# SSB_Transceiver_Speaker_Amplifier.net
KiCad netlist of a schematic drawn in EAGLE
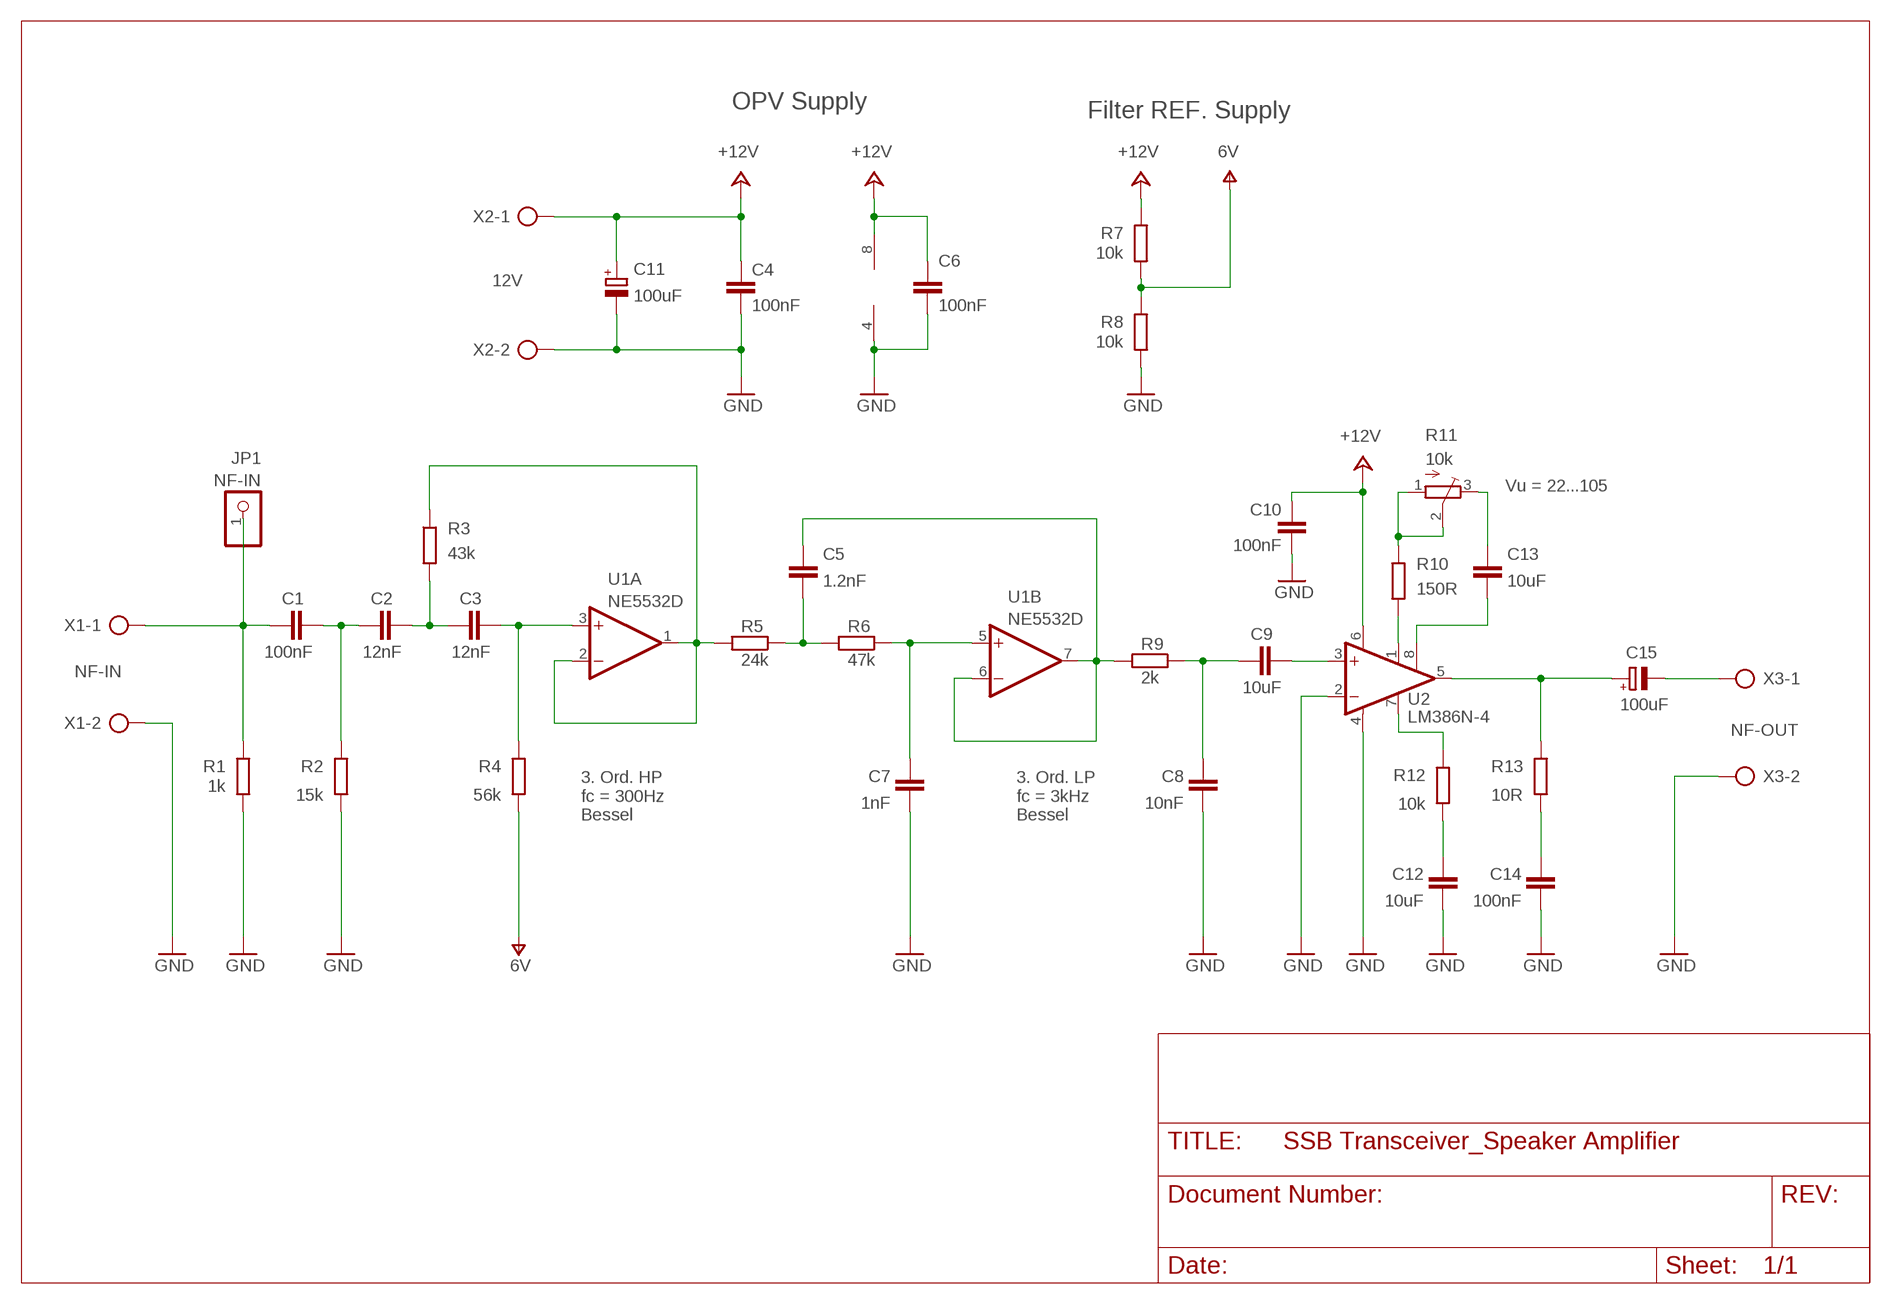
[diagram p0: schematic, sheet 1]

(export (version "E")
  (design (tool "Eeschema 10.0.6"))
  (components
    (comp (ref "C1")
      (value "100nF")
      (footprint "eagle-import:C0805")
      (libsource (lib "eagle-import") (part "C-EUC0805"))
    )
    (comp (ref "C2")
      (value "12nF")
      (footprint "eagle-import:C0805")
      (libsource (lib "eagle-import") (part "C-EUC0805"))
    )
    (comp (ref "C3")
      (value "12nF")
      (footprint "eagle-import:C0805")
      (libsource (lib "eagle-import") (part "C-EUC0805"))
    )
    (comp (ref "C4")
      (value "100nF")
      (footprint "eagle-import:C0805")
      (libsource (lib "eagle-import") (part "C-EUC0805"))
    )
    (comp (ref "C5")
      (value "1.2nF")
      (footprint "eagle-import:C0805")
      (libsource (lib "eagle-import") (part "C-EUC0805"))
    )
    (comp (ref "C6")
      (value "100nF")
      (footprint "eagle-import:C0805")
      (libsource (lib "eagle-import") (part "C-EUC0805"))
    )
    (comp (ref "C7")
      (value "1nF")
      (footprint "eagle-import:C0805")
      (libsource (lib "eagle-import") (part "C-EUC0805"))
    )
    (comp (ref "C8")
      (value "10nF")
      (footprint "eagle-import:C0805")
      (libsource (lib "eagle-import") (part "C-EUC0805"))
    )
    (comp (ref "C9")
      (value "10uF")
      (footprint "eagle-import:C0805")
      (libsource (lib "eagle-import") (part "C-EUC0805"))
    )
    (comp (ref "C10")
      (value "100nF")
      (footprint "eagle-import:C0805")
      (libsource (lib "eagle-import") (part "C-EUC0805"))
    )
    (comp (ref "C11")
      (value "100uF")
      (footprint "eagle-import:E2,5-6")
      (libsource (lib "eagle-import") (part "CPOL-EUE2.5-6"))
    )
    (comp (ref "C12")
      (value "10uF")
      (footprint "eagle-import:C0805")
      (libsource (lib "eagle-import") (part "C-EUC0805"))
    )
    (comp (ref "C13")
      (value "10uF")
      (footprint "eagle-import:C0805")
      (libsource (lib "eagle-import") (part "C-EUC0805"))
    )
    (comp (ref "C14")
      (value "100nF")
      (footprint "eagle-import:C0805")
      (libsource (lib "eagle-import") (part "C-EUC0805"))
    )
    (comp (ref "C15")
      (value "100uF")
      (footprint "eagle-import:E2,5-6")
      (libsource (lib "eagle-import") (part "CPOL-EUE2.5-6"))
    )
    (comp (ref "JP1")
      (value "NF-IN")
      (footprint "eagle-import:1X01")
      (libsource (lib "eagle-import") (part "PINHD-1X1"))
    )
    (comp (ref "R1")
      (value "1k")
      (footprint "eagle-import:R0805")
      (libsource (lib "eagle-import") (part "R-EU_R0805"))
    )
    (comp (ref "R2")
      (value "15k")
      (footprint "eagle-import:R0805")
      (libsource (lib "eagle-import") (part "R-EU_R0805"))
    )
    (comp (ref "R3")
      (value "43k")
      (footprint "eagle-import:R0805")
      (libsource (lib "eagle-import") (part "R-EU_R0805"))
    )
    (comp (ref "R4")
      (value "56k")
      (footprint "eagle-import:R0805")
      (libsource (lib "eagle-import") (part "R-EU_R0805"))
    )
    (comp (ref "R5")
      (value "24k")
      (footprint "eagle-import:R0805")
      (libsource (lib "eagle-import") (part "R-EU_R0805"))
    )
    (comp (ref "R6")
      (value "47k")
      (footprint "eagle-import:R0805")
      (libsource (lib "eagle-import") (part "R-EU_R0805"))
    )
    (comp (ref "R7")
      (value "10k")
      (footprint "eagle-import:R0805")
      (libsource (lib "eagle-import") (part "R-EU_R0805"))
    )
    (comp (ref "R8")
      (value "10k")
      (footprint "eagle-import:R0805")
      (libsource (lib "eagle-import") (part "R-EU_R0805"))
    )
    (comp (ref "R9")
      (value "2k")
      (footprint "eagle-import:R0805")
      (libsource (lib "eagle-import") (part "R-EU_R0805"))
    )
    (comp (ref "R10")
      (value "150R")
      (footprint "eagle-import:R0805")
      (libsource (lib "eagle-import") (part "R-EU_R0805"))
    )
    (comp (ref "R11")
      (value "10k")
      (footprint "eagle-import:3223G")
      (libsource (lib "eagle-import") (part "TRIM_EU-3223G"))
    )
    (comp (ref "R12")
      (value "10k")
      (footprint "eagle-import:R0805")
      (libsource (lib "eagle-import") (part "R-EU_R0805"))
    )
    (comp (ref "R13")
      (value "10R")
      (footprint "eagle-import:R0805")
      (libsource (lib "eagle-import") (part "R-EU_R0805"))
    )
    (comp (ref "U1")
      (value "NE5532D")
      (footprint "eagle-import:SO08")
      (libsource (lib "eagle-import") (part "NE5532D"))
    )
    (comp (ref "U2")
      (value "LM386N-4")
      (footprint "eagle-import:DIL08")
      (libsource (lib "eagle-import") (part "LM386?-N4"))
    )
    (comp (ref "X1")
      (value "NF-IN")
      (footprint "eagle-import:AK300_2")
      (libsource (lib "eagle-import") (part "AK300/2"))
    )
    (comp (ref "X2")
      (value "12V")
      (footprint "eagle-import:AK300_2")
      (libsource (lib "eagle-import") (part "AK300/2"))
    )
    (comp (ref "X3")
      (value "NF-OUT")
      (footprint "eagle-import:AK300_2")
      (libsource (lib "eagle-import") (part "AK300/2"))
    )
  )
  (nets
    (net (code "1") (name "+12V") (class "Default")
      (node (ref "C10") (pin "2") (pinfunction "2_2") (pintype "passive"))
      (node (ref "C11") (pin "+") (pinfunction "+_+") (pintype "passive"))
      (node (ref "C4") (pin "2") (pinfunction "2_2") (pintype "passive"))
      (node (ref "C6") (pin "2") (pinfunction "2_2") (pintype "passive"))
      (node (ref "R7") (pin "1") (pinfunction "1_1") (pintype "passive"))
      (node (ref "U1") (pin "8") (pinfunction "V+_8") (pintype "power_in"))
      (node (ref "U2") (pin "6") (pinfunction "VS_6") (pintype "power_in"))
      (node (ref "X2") (pin "1") (pinfunction "KL_1") (pintype "passive"))
    )
    (net (code "2") (name "6V") (class "Default")
      (node (ref "R4") (pin "2") (pinfunction "2_2") (pintype "passive"))
      (node (ref "R7") (pin "2") (pinfunction "2_2") (pintype "passive"))
      (node (ref "R8") (pin "1") (pinfunction "1_1") (pintype "passive"))
    )
    (net (code "3") (name "GND") (class "Default")
      (node (ref "C10") (pin "1") (pinfunction "1_1") (pintype "passive"))
      (node (ref "C11") (pin "-") (pinfunction "-_-") (pintype "passive"))
      (node (ref "C12") (pin "1") (pinfunction "1_1") (pintype "passive"))
      (node (ref "C14") (pin "1") (pinfunction "1_1") (pintype "passive"))
      (node (ref "C4") (pin "1") (pinfunction "1_1") (pintype "passive"))
      (node (ref "C6") (pin "1") (pinfunction "1_1") (pintype "passive"))
      (node (ref "C7") (pin "1") (pinfunction "1_1") (pintype "passive"))
      (node (ref "C8") (pin "1") (pinfunction "1_1") (pintype "passive"))
      (node (ref "R1") (pin "2") (pinfunction "2_2") (pintype "passive"))
      (node (ref "R2") (pin "2") (pinfunction "2_2") (pintype "passive"))
      (node (ref "R8") (pin "2") (pinfunction "2_2") (pintype "passive"))
      (node (ref "U1") (pin "4") (pinfunction "V-_4") (pintype "power_in"))
      (node (ref "U2") (pin "2") (pinfunction "-IN_2") (pintype "input"))
      (node (ref "U2") (pin "4") (pinfunction "GND_4") (pintype "power_in"))
      (node (ref "X1") (pin "2") (pinfunction "KL_2") (pintype "passive"))
      (node (ref "X2") (pin "2") (pinfunction "KL_2") (pintype "passive"))
      (node (ref "X3") (pin "2") (pinfunction "KL_2") (pintype "passive"))
    )
    (net (code "4") (name "Net-(C1-Pad2)") (class "Default")
      (node (ref "C1") (pin "2") (pinfunction "2_2") (pintype "passive"))
      (node (ref "C2") (pin "1") (pinfunction "1_1") (pintype "passive"))
      (node (ref "R2") (pin "1") (pinfunction "1_1") (pintype "passive"))
    )
    (net (code "5") (name "Net-(C2-Pad2)") (class "Default")
      (node (ref "C2") (pin "2") (pinfunction "2_2") (pintype "passive"))
      (node (ref "C3") (pin "1") (pinfunction "1_1") (pintype "passive"))
      (node (ref "R3") (pin "2") (pinfunction "2_2") (pintype "passive"))
    )
    (net (code "6") (name "Net-(C5-Pad1)") (class "Default")
      (node (ref "C5") (pin "1") (pinfunction "1_1") (pintype "passive"))
      (node (ref "R5") (pin "1") (pinfunction "1_1") (pintype "passive"))
      (node (ref "R6") (pin "2") (pinfunction "2_2") (pintype "passive"))
    )
    (net (code "7") (name "Net-(C8-Pad2)") (class "Default")
      (node (ref "C8") (pin "2") (pinfunction "2_2") (pintype "passive"))
      (node (ref "C9") (pin "1") (pinfunction "1_1") (pintype "passive"))
      (node (ref "R9") (pin "1") (pinfunction "1_1") (pintype "passive"))
    )
    (net (code "8") (name "Net-(C12-Pad2)") (class "Default")
      (node (ref "C12") (pin "2") (pinfunction "2_2") (pintype "passive"))
      (node (ref "R12") (pin "2") (pinfunction "2_2") (pintype "passive"))
    )
    (net (code "9") (name "Net-(C13-Pad1)") (class "Default")
      (node (ref "C13") (pin "1") (pinfunction "1_1") (pintype "passive"))
      (node (ref "U2") (pin "8") (pinfunction "GAIN_8") (pintype "passive"))
    )
    (net (code "10") (name "Net-(C14-Pad2)") (class "Default")
      (node (ref "C14") (pin "2") (pinfunction "2_2") (pintype "passive"))
      (node (ref "R13") (pin "2") (pinfunction "2_2") (pintype "passive"))
    )
    (net (code "11") (name "Net-(R10-Pad2)") (class "Default")
      (node (ref "R10") (pin "2") (pinfunction "2_2") (pintype "passive"))
      (node (ref "U2") (pin "1") (pinfunction "GAIN_1") (pintype "passive"))
    )
    (net (code "12") (name "Net-(R11-A)") (class "Default")
      (node (ref "R10") (pin "1") (pinfunction "1_1") (pintype "passive"))
      (node (ref "R11") (pin "1") (pinfunction "A_1") (pintype "passive"))
      (node (ref "R11") (pin "2") (pinfunction "S_2") (pintype "passive"))
    )
    (net (code "13") (name "Net-(R11-E)") (class "Default")
      (node (ref "C13") (pin "2") (pinfunction "2_2") (pintype "passive"))
      (node (ref "R11") (pin "3") (pinfunction "E_3") (pintype "passive"))
    )
    (net (code "14") (name "Net-(U1A-+IN)") (class "Default")
      (node (ref "C3") (pin "2") (pinfunction "2_2") (pintype "passive"))
      (node (ref "R4") (pin "1") (pinfunction "1_1") (pintype "passive"))
      (node (ref "U1") (pin "3") (pinfunction "+IN_3") (pintype "input"))
    )
    (net (code "15") (name "Net-(U1A--IN)") (class "Default")
      (node (ref "R3") (pin "1") (pinfunction "1_1") (pintype "passive"))
      (node (ref "R5") (pin "2") (pinfunction "2_2") (pintype "passive"))
      (node (ref "U1") (pin "1") (pinfunction "OUT_1") (pintype "output"))
      (node (ref "U1") (pin "2") (pinfunction "-IN_2") (pintype "input"))
    )
    (net (code "16") (name "Net-(U1B-+IN)") (class "Default")
      (node (ref "C7") (pin "2") (pinfunction "2_2") (pintype "passive"))
      (node (ref "R6") (pin "1") (pinfunction "1_1") (pintype "passive"))
      (node (ref "U1") (pin "5") (pinfunction "+IN_5") (pintype "input"))
    )
    (net (code "17") (name "Net-(U1B--IN)") (class "Default")
      (node (ref "C5") (pin "2") (pinfunction "2_2") (pintype "passive"))
      (node (ref "R9") (pin "2") (pinfunction "2_2") (pintype "passive"))
      (node (ref "U1") (pin "6") (pinfunction "-IN_6") (pintype "input"))
      (node (ref "U1") (pin "7") (pinfunction "OUT_7") (pintype "output"))
    )
    (net (code "18") (name "Net-(U2-+IN)") (class "Default")
      (node (ref "C9") (pin "2") (pinfunction "2_2") (pintype "passive"))
      (node (ref "U2") (pin "3") (pinfunction "+IN_3") (pintype "input"))
    )
    (net (code "19") (name "Net-(U2-BYPASS)") (class "Default")
      (node (ref "R12") (pin "1") (pinfunction "1_1") (pintype "passive"))
      (node (ref "U2") (pin "7") (pinfunction "BYPASS_7") (pintype "passive"))
    )
    (net (code "20") (name "Net-(U2-OUT)") (class "Default")
      (node (ref "C15") (pin "+") (pinfunction "+_+") (pintype "passive"))
      (node (ref "R13") (pin "1") (pinfunction "1_1") (pintype "passive"))
      (node (ref "U2") (pin "5") (pinfunction "OUT_5") (pintype "output"))
    )
    (net (code "21") (name "Net-(X1A-KL)") (class "Default")
      (node (ref "C1") (pin "1") (pinfunction "1_1") (pintype "passive"))
      (node (ref "JP1") (pin "1") (pinfunction "1_1") (pintype "passive"))
      (node (ref "R1") (pin "1") (pinfunction "1_1") (pintype "passive"))
      (node (ref "X1") (pin "1") (pinfunction "KL_1") (pintype "passive"))
    )
    (net (code "22") (name "Net-(X3A-KL)") (class "Default")
      (node (ref "C15") (pin "-") (pinfunction "-_-") (pintype "passive"))
      (node (ref "X3") (pin "1") (pinfunction "KL_1") (pintype "passive"))
    )
  )
)
